# Power_Supply_Regulation.net
KiCad netlist of a schematic drawn in Altium Designer
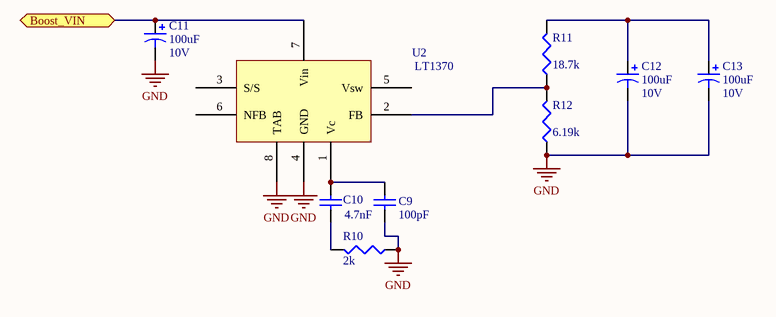
[diagram p0: Power_Supply_Regulation.SchDoc]

(export (version "E")
  (design (tool "Eeschema 10.0.6"))
  (components
    (comp (ref "C9")
      (value "100pF")
      (footprint "1608[0603]")
      (description "Capacitor (Semiconductor SIM Model)")
      (fields (field (name "Comment") "Cap Semi") (field (name "PUBLISHER") "Altium Limited"))
      (libsource (lib "Miscellaneous Devices") (part "Cap Semi"))
    )
    (comp (ref "C10")
      (value "4.7nF")
      (footprint "1608[0603]")
      (description "Capacitor (Semiconductor SIM Model)")
      (fields (field (name "Comment") "Cap Semi") (field (name "PUBLISHER") "Altium Limited"))
      (libsource (lib "Miscellaneous Devices") (part "Cap Semi"))
    )
    (comp (ref "C11")
      (value "100uF")
      (footprint "1812")
      (description "Polarized Capacitor (Surface Mount)")
      (fields
        (field (name "VOLTAGE") "10V")
        (field (name "PART") "AVX TPSD107M010R0100")
        (field (name "Comment") "Cap Pol3")
        (field (name "PUBLISHER") "Altium Limited")
      )
      (libsource (lib "Miscellaneous Devices") (part "Cap Pol3"))
    )
    (comp (ref "C12")
      (value "100uF")
      (footprint "1812")
      (description "Polarized Capacitor (Surface Mount)")
      (fields
        (field (name "VOLTAGE") "10V")
        (field (name "PART") "AVX TPSD107M010R0100")
        (field (name "Comment") "Cap Pol3")
        (field (name "PUBLISHER") "Altium Limited")
      )
      (libsource (lib "Miscellaneous Devices") (part "Cap Pol3"))
    )
    (comp (ref "C13")
      (value "100uF")
      (footprint "1812")
      (description "Polarized Capacitor (Surface Mount)")
      (fields
        (field (name "VOLTAGE") "10V")
        (field (name "PART") "AVX TPSD107M010R0100")
        (field (name "Comment") "Cap Pol3")
        (field (name "PUBLISHER") "Altium Limited")
      )
      (libsource (lib "Miscellaneous Devices") (part "Cap Pol3"))
    )
    (comp (ref "R10")
      (value "2k")
      (footprint "J1-0603")
      (description "Resistor")
      (fields (field (name "Comment") "Res3") (field (name "PUBLISHER") "Altium Limited"))
      (libsource (lib "Miscellaneous Devices") (part "Res3"))
    )
    (comp (ref "R11")
      (value "18.7k")
      (footprint "J1-0603")
      (description "Resistor")
      (fields (field (name "Comment") "Res3") (field (name "PUBLISHER") "Altium Limited"))
      (libsource (lib "Miscellaneous Devices") (part "Res3"))
    )
    (comp (ref "R12")
      (value "6.19k")
      (footprint "J1-0603")
      (description "Resistor")
      (fields (field (name "Comment") "Res3") (field (name "PUBLISHER") "Altium Limited"))
      (libsource (lib "Miscellaneous Devices") (part "Res3"))
    )
    (comp (ref "U2")
      (value "LT1370")
      (footprint "TO127P1520-8L")
      (description "500kHz High Efficiency 6A Switching Regulator")
      (libsource (lib "Power_Component_Symbols") (part "LT1370"))
    )
  )
  (nets
    (net (code "1") (name "/Boost_VIN") (class "Default")
      (node (ref "C11") (pin "1") (pinfunction "1_1") (pintype "passive"))
      (node (ref "U2") (pin "7") (pinfunction "Vin_7") (pintype "passive"))
    )
    (net (code "2") (name "GND") (class "Default")
      (node (ref "C11") (pin "2") (pinfunction "2_2") (pintype "passive"))
      (node (ref "C12") (pin "2") (pinfunction "2_2") (pintype "passive"))
      (node (ref "C13") (pin "2") (pinfunction "2_2") (pintype "passive"))
      (node (ref "C9") (pin "1") (pinfunction "1_1") (pintype "passive"))
      (node (ref "R10") (pin "1") (pinfunction "1_1") (pintype "passive"))
      (node (ref "R12") (pin "1") (pinfunction "1_1") (pintype "passive"))
      (node (ref "U2") (pin "4") (pinfunction "GND_4") (pintype "passive"))
      (node (ref "U2") (pin "8") (pinfunction "TAB_8") (pintype "passive"))
    )
    (net (code "3") (name "Net-(C10-Pad1)") (class "Default")
      (node (ref "C10") (pin "1") (pinfunction "1_1") (pintype "passive"))
      (node (ref "R10") (pin "2") (pinfunction "2_2") (pintype "passive"))
    )
    (net (code "4") (name "Net-(C12-Pad1)") (class "Default")
      (node (ref "C12") (pin "1") (pinfunction "1_1") (pintype "passive"))
      (node (ref "C13") (pin "1") (pinfunction "1_1") (pintype "passive"))
      (node (ref "R11") (pin "2") (pinfunction "2_2") (pintype "passive"))
    )
    (net (code "5") (name "Net-(U2-FB)") (class "Default")
      (node (ref "R11") (pin "1") (pinfunction "1_1") (pintype "passive"))
      (node (ref "R12") (pin "2") (pinfunction "2_2") (pintype "passive"))
      (node (ref "U2") (pin "2") (pinfunction "FB_2") (pintype "passive"))
    )
    (net (code "6") (name "Net-(U2-Vc)") (class "Default")
      (node (ref "C10") (pin "2") (pinfunction "2_2") (pintype "passive"))
      (node (ref "C9") (pin "2") (pinfunction "2_2") (pintype "passive"))
      (node (ref "U2") (pin "1") (pinfunction "Vc_1") (pintype "passive"))
    )
    (net (code "7") (name "unconnected-(U2-NFB-Pad6)") (class "Default")
      (node (ref "U2") (pin "6") (pinfunction "NFB_6") (pintype "passive"))
    )
    (net (code "8") (name "unconnected-(U2-S{slash}S-Pad3)") (class "Default")
      (node (ref "U2") (pin "3") (pinfunction "S/S_3") (pintype "passive"))
    )
    (net (code "9") (name "unconnected-(U2-Vsw-Pad5)") (class "Default")
      (node (ref "U2") (pin "5") (pinfunction "Vsw_5") (pintype "passive"))
    )
  )
)
